# ESP32Cam-Programmer-Public.net
KiCad netlist of a schematic drawn in EAGLE
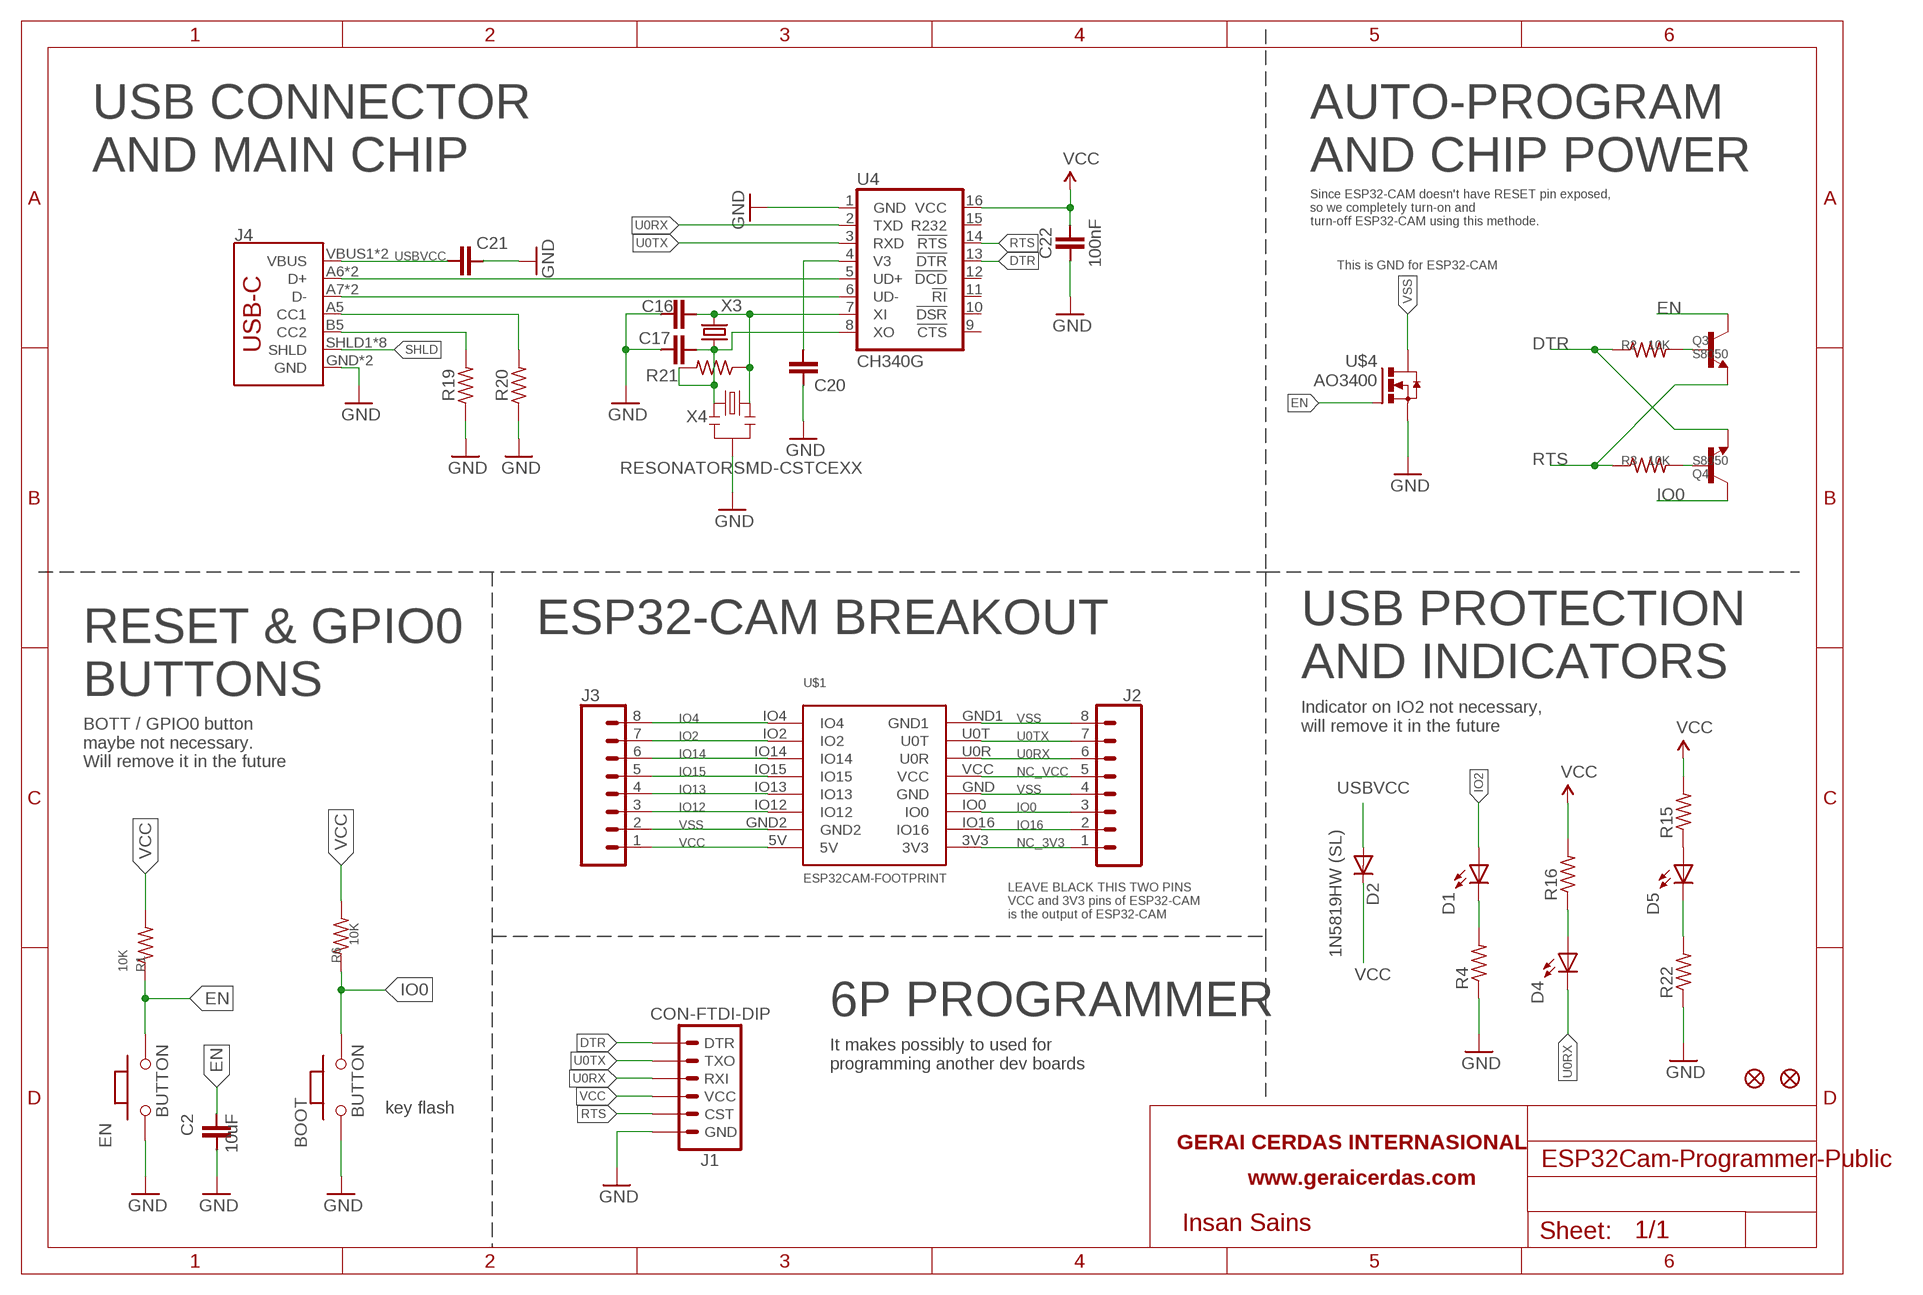
[diagram p0: schematic, sheet 1]

(export (version "E")
  (design (tool "Eeschema 10.0.6"))
  (components
    (comp (ref "BOOT")
      (value "BUTTON")
      (footprint "eagle-import:157SW")
      (libsource (lib "eagle-import") (part "PB157"))
    )
    (comp (ref "C2")
      (value "10uF")
      (footprint "eagle-import:C0603")
      (libsource (lib "eagle-import") (part "CAPACITOR-SMD0603"))
    )
    (comp (ref "C16")
      (value "10pF")
      (footprint "eagle-import:C0603")
      (libsource (lib "eagle-import") (part "CAPACITOR-SMD0603"))
    )
    (comp (ref "C17")
      (value "10pF")
      (footprint "eagle-import:C0603")
      (libsource (lib "eagle-import") (part "CAPACITOR-SMD0603"))
    )
    (comp (ref "C20")
      (value "10nF")
      (footprint "eagle-import:C0603")
      (libsource (lib "eagle-import") (part "CAPACITOR-SMD0603"))
    )
    (comp (ref "C21")
      (value "100nF")
      (footprint "eagle-import:C0603")
      (libsource (lib "eagle-import") (part "CAPACITOR-SMD0603"))
    )
    (comp (ref "C22")
      (value "100nF")
      (footprint "eagle-import:C0603")
      (libsource (lib "eagle-import") (part "CAPACITOR-SMD0603"))
    )
    (comp (ref "D1")
      (value "Yellow")
      (footprint "eagle-import:LED0805")
      (libsource (lib "eagle-import") (part "LED-SMD0805"))
    )
    (comp (ref "D2")
      (value "1N5819HW (SL)")
      (footprint "eagle-import:SOD-323")
      (fields (field (name "MANUFACTURER_PART_NUMBER") "1N4148WS"))
      (libsource (lib "eagle-import") (part "DIODE-1N4148-323"))
    )
    (comp (ref "D4")
      (value "GREEN")
      (footprint "eagle-import:LED0805")
      (libsource (lib "eagle-import") (part "LED-SMD0805"))
    )
    (comp (ref "D5")
      (value "Yellow")
      (footprint "eagle-import:LED0805")
      (libsource (lib "eagle-import") (part "LED-SMD0805"))
    )
    (comp (ref "EN")
      (value "BUTTON")
      (footprint "eagle-import:157SW")
      (libsource (lib "eagle-import") (part "PB157"))
    )
    (comp (ref "J1")
      (value "CON-FTDI-DIP")
      (footprint "eagle-import:CON-FTDI")
      (libsource (lib "eagle-import") (part "CON-FTDI-DIP"))
    )
    (comp (ref "J2")
      (value "CONN_08\"")
      (footprint "eagle-import:1X08")
      (libsource (lib "eagle-import") (part "CONN_08{dblquote}"))
    )
    (comp (ref "J3")
      (value "CONN_08\"")
      (footprint "eagle-import:1X08")
      (libsource (lib "eagle-import") (part "CONN_08{dblquote}"))
    )
    (comp (ref "J4")
      (value "USB_C16PIN")
      (footprint "eagle-import:USB-C-16P")
      (libsource (lib "eagle-import") (part "USB_C16PIN"))
    )
    (comp (ref "JP8")
      (value "FIDUCIAL1X2")
      (footprint "eagle-import:FIDUCIAL-1X2")
      (libsource (lib "eagle-import") (part "FIDUCIAL1X2"))
    )
    (comp (ref "JP9")
      (value "FIDUCIAL1X2")
      (footprint "eagle-import:FIDUCIAL-1X2")
      (libsource (lib "eagle-import") (part "FIDUCIAL1X2"))
    )
    (comp (ref "Q3")
      (value "S8050")
      (footprint "eagle-import:SOT-23")
      (libsource (lib "eagle-import") (part "TRANSISTOR-NPN-S8050"))
    )
    (comp (ref "Q4")
      (value "S8050")
      (footprint "eagle-import:SOT-23")
      (libsource (lib "eagle-import") (part "TRANSISTOR-NPN-S8050"))
    )
    (comp (ref "R1")
      (value "10K")
      (footprint "eagle-import:R0603")
      (libsource (lib "eagle-import") (part "RESISTOR-SMD0603"))
    )
    (comp (ref "R2")
      (value "10K")
      (footprint "eagle-import:R0603")
      (libsource (lib "eagle-import") (part "RESISTOR-SMD0603"))
    )
    (comp (ref "R3")
      (value "10K")
      (footprint "eagle-import:R0603")
      (libsource (lib "eagle-import") (part "RESISTOR-SMD0603"))
    )
    (comp (ref "R4")
      (value "1K")
      (footprint "eagle-import:R0603")
      (libsource (lib "eagle-import") (part "RESISTOR-SMD0603"))
    )
    (comp (ref "R6")
      (value "10K")
      (footprint "eagle-import:R0603")
      (libsource (lib "eagle-import") (part "RESISTOR-SMD0603"))
    )
    (comp (ref "R15")
      (value "330")
      (footprint "eagle-import:R0603")
      (libsource (lib "eagle-import") (part "RESISTOR-SMD0603"))
    )
    (comp (ref "R16")
      (value "330")
      (footprint "eagle-import:R0603")
      (libsource (lib "eagle-import") (part "RESISTOR-SMD0603"))
    )
    (comp (ref "R19")
      (value "5.1k")
      (footprint "eagle-import:R0603")
      (libsource (lib "eagle-import") (part "RESISTOR-SMD0603"))
    )
    (comp (ref "R20")
      (value "5.1k")
      (footprint "eagle-import:R0603")
      (libsource (lib "eagle-import") (part "RESISTOR-SMD0603"))
    )
    (comp (ref "R21")
      (value "RESISTOR-SMD0603")
      (footprint "eagle-import:R0603")
      (libsource (lib "eagle-import") (part "RESISTOR-SMD0603"))
    )
    (comp (ref "R22")
      (value "1K")
      (footprint "eagle-import:R0603")
      (libsource (lib "eagle-import") (part "RESISTOR-SMD0603"))
    )
    (comp (ref "U$1")
      (value "ESP32CAM-FOOTPRINT")
      (footprint "eagle-import:ESP32CAM")
      (libsource (lib "eagle-import") (part "ESP32CAM-FOOTPRINT"))
    )
    (comp (ref "U$4")
      (value "AO3400")
      (footprint "eagle-import:SOT-23")
      (libsource (lib "eagle-import") (part "AO3400"))
    )
    (comp (ref "U$13")
      (value "FRAME")
      (footprint "eagle-import:A4-HOR")
      (libsource (lib "eagle-import") (part "FRAME"))
    )
    (comp (ref "U4")
      (value "CH340G")
      (footprint "eagle-import:SO016")
      (libsource (lib "eagle-import") (part "CH340GSMD"))
    )
    (comp (ref "X3")
      (value "XTAL-SMD")
      (footprint "eagle-import:SMD-CRYSTAL")
      (libsource (lib "eagle-import") (part "XTAL-SMD"))
    )
    (comp (ref "X4")
      (value "RESONATORSMD-CSTCEXX")
      (footprint "eagle-import:CSTCE_")
      (libsource (lib "eagle-import") (part "RESONATORSMD-CSTCEXX"))
    )
  )
  (nets
    (net (code "1") (name "/IO4") (class "Default")
      (node (ref "J3") (pin "8") (pinfunction "8_8") (pintype "passive"))
      (node (ref "U$1") (pin "IO4") (pinfunction "IO4_IO4") (pintype "bidirectional"))
    )
    (net (code "2") (name "/IO12") (class "Default")
      (node (ref "J3") (pin "3") (pinfunction "3_3") (pintype "passive"))
      (node (ref "U$1") (pin "IO12") (pinfunction "IO12_IO12") (pintype "bidirectional"))
    )
    (net (code "3") (name "/IO13") (class "Default")
      (node (ref "J3") (pin "4") (pinfunction "4_4") (pintype "passive"))
      (node (ref "U$1") (pin "IO13") (pinfunction "IO13_IO13") (pintype "bidirectional"))
    )
    (net (code "4") (name "/IO14") (class "Default")
      (node (ref "J3") (pin "6") (pinfunction "6_6") (pintype "passive"))
      (node (ref "U$1") (pin "IO14") (pinfunction "IO14_IO14") (pintype "bidirectional"))
    )
    (net (code "5") (name "/IO15") (class "Default")
      (node (ref "J3") (pin "5") (pinfunction "5_5") (pintype "passive"))
      (node (ref "U$1") (pin "IO15") (pinfunction "IO15_IO15") (pintype "bidirectional"))
    )
    (net (code "6") (name "/IO16") (class "Default")
      (node (ref "J2") (pin "2") (pinfunction "2_2") (pintype "passive"))
      (node (ref "U$1") (pin "IO16") (pinfunction "IO16_IO16") (pintype "bidirectional"))
    )
    (net (code "7") (name "/NC_3V3") (class "Default")
      (node (ref "J2") (pin "1") (pinfunction "1_1") (pintype "passive"))
      (node (ref "U$1") (pin "3V3") (pinfunction "3V3_3V3") (pintype "bidirectional"))
    )
    (net (code "8") (name "/NC_VCC") (class "Default")
      (node (ref "J2") (pin "5") (pinfunction "5_5") (pintype "passive"))
      (node (ref "U$1") (pin "VCC") (pinfunction "VCC_VCC") (pintype "bidirectional"))
    )
    (net (code "9") (name "/USBVCC") (class "Default")
      (node (ref "C21") (pin "1") (pinfunction "1_1") (pintype "passive"))
      (node (ref "D2") (pin "A") (pinfunction "A_A") (pintype "passive"))
      (node (ref "J4") (pin "VBUS1") (pinfunction "VBUS_VBUS1") (pintype "bidirectional"))
      (node (ref "J4") (pin "VBUS2") (pinfunction "VBUS_VBUS2") (pintype "bidirectional"))
    )
    (net (code "10") (name "DTR") (class "Default")
      (node (ref "J1") (pin "DTR") (pinfunction "DTR_DTR") (pintype "passive"))
      (node (ref "Q4") (pin "2") (pinfunction "E_2") (pintype "passive"))
      (node (ref "R2") (pin "1") (pinfunction "1_1") (pintype "passive"))
      (node (ref "U4") (pin "13") (pinfunction "~{DTR}_13") (pintype "bidirectional"))
    )
    (net (code "11") (name "EN") (class "Default")
      (node (ref "C2") (pin "2") (pinfunction "2_2") (pintype "passive"))
      (node (ref "EN") (pin "2") (pinfunction "2_2") (pintype "passive"))
      (node (ref "Q3") (pin "3") (pinfunction "C_3") (pintype "passive"))
      (node (ref "R1") (pin "1") (pinfunction "1_1") (pintype "passive"))
      (node (ref "U$4") (pin "1") (pinfunction "G_1") (pintype "passive"))
    )
    (net (code "12") (name "GND") (class "Default")
      (node (ref "BOOT") (pin "1") (pinfunction "1_1") (pintype "passive"))
      (node (ref "C16") (pin "1") (pinfunction "1_1") (pintype "passive"))
      (node (ref "C17") (pin "1") (pinfunction "1_1") (pintype "passive"))
      (node (ref "C2") (pin "1") (pinfunction "1_1") (pintype "passive"))
      (node (ref "C20") (pin "2") (pinfunction "2_2") (pintype "passive"))
      (node (ref "C21") (pin "2") (pinfunction "2_2") (pintype "passive"))
      (node (ref "C22") (pin "1") (pinfunction "1_1") (pintype "passive"))
      (node (ref "EN") (pin "1") (pinfunction "1_1") (pintype "passive"))
      (node (ref "J1") (pin "GND") (pinfunction "GND_GND") (pintype "passive"))
      (node (ref "J4") (pin "GND") (pinfunction "GND_GND") (pintype "bidirectional"))
      (node (ref "J4") (pin "GND2") (pinfunction "GND_GND2") (pintype "bidirectional"))
      (node (ref "R19") (pin "1") (pinfunction "1_1") (pintype "passive"))
      (node (ref "R20") (pin "1") (pinfunction "1_1") (pintype "passive"))
      (node (ref "R22") (pin "1") (pinfunction "1_1") (pintype "passive"))
      (node (ref "R4") (pin "1") (pinfunction "1_1") (pintype "passive"))
      (node (ref "U$4") (pin "2") (pinfunction "S_2") (pintype "passive"))
      (node (ref "U4") (pin "1") (pinfunction "GND_1") (pintype "bidirectional"))
      (node (ref "X4") (pin "2") (pinfunction "2_2") (pintype "passive"))
    )
    (net (code "13") (name "IO0") (class "Default")
      (node (ref "BOOT") (pin "2") (pinfunction "2_2") (pintype "passive"))
      (node (ref "J2") (pin "3") (pinfunction "3_3") (pintype "passive"))
      (node (ref "Q4") (pin "3") (pinfunction "C_3") (pintype "passive"))
      (node (ref "R6") (pin "1") (pinfunction "1_1") (pintype "passive"))
      (node (ref "U$1") (pin "IO0") (pinfunction "IO0_IO0") (pintype "bidirectional"))
    )
    (net (code "14") (name "IO2") (class "Default")
      (node (ref "D1") (pin "A") (pinfunction "A_A") (pintype "passive"))
      (node (ref "J3") (pin "7") (pinfunction "7_7") (pintype "passive"))
      (node (ref "U$1") (pin "IO2") (pinfunction "IO2_IO2") (pintype "bidirectional"))
    )
    (net (code "15") (name "Net-(D1-PadC)") (class "Default")
      (node (ref "D1") (pin "C") (pinfunction "C_C") (pintype "passive"))
      (node (ref "R4") (pin "2") (pinfunction "2_2") (pintype "passive"))
    )
    (net (code "16") (name "Net-(D4-PadA)") (class "Default")
      (node (ref "D4") (pin "A") (pinfunction "A_A") (pintype "passive"))
      (node (ref "R16") (pin "1") (pinfunction "1_1") (pintype "passive"))
    )
    (net (code "17") (name "Net-(D5-PadA)") (class "Default")
      (node (ref "D5") (pin "A") (pinfunction "A_A") (pintype "passive"))
      (node (ref "R15") (pin "1") (pinfunction "1_1") (pintype "passive"))
    )
    (net (code "18") (name "Net-(D5-PadC)") (class "Default")
      (node (ref "D5") (pin "C") (pinfunction "C_C") (pintype "passive"))
      (node (ref "R22") (pin "2") (pinfunction "2_2") (pintype "passive"))
    )
    (net (code "19") (name "Net-(J4-CC1)") (class "Default")
      (node (ref "J4") (pin "A5") (pinfunction "CC1_A5") (pintype "bidirectional"))
      (node (ref "R20") (pin "2") (pinfunction "2_2") (pintype "passive"))
    )
    (net (code "20") (name "Net-(J4-CC2)") (class "Default")
      (node (ref "J4") (pin "B5") (pinfunction "CC2_B5") (pintype "bidirectional"))
      (node (ref "R19") (pin "2") (pinfunction "2_2") (pintype "passive"))
    )
    (net (code "21") (name "Net-(Q3-B)") (class "Default")
      (node (ref "Q3") (pin "1") (pinfunction "B_1") (pintype "passive"))
      (node (ref "R2") (pin "2") (pinfunction "2_2") (pintype "passive"))
    )
    (net (code "22") (name "Net-(Q4-B)") (class "Default")
      (node (ref "Q4") (pin "1") (pinfunction "B_1") (pintype "passive"))
      (node (ref "R3") (pin "2") (pinfunction "2_2") (pintype "passive"))
    )
    (net (code "23") (name "Net-(U4-UD+)") (class "Default")
      (node (ref "J4") (pin "A6") (pinfunction "D+_A6") (pintype "bidirectional"))
      (node (ref "J4") (pin "B6") (pinfunction "D+_B6") (pintype "bidirectional"))
      (node (ref "U4") (pin "5") (pinfunction "UD+_5") (pintype "bidirectional"))
    )
    (net (code "24") (name "Net-(U4-UD-)") (class "Default")
      (node (ref "J4") (pin "A7") (pinfunction "D-_A7") (pintype "bidirectional"))
      (node (ref "J4") (pin "B7") (pinfunction "D-_B7") (pintype "bidirectional"))
      (node (ref "U4") (pin "6") (pinfunction "UD-_6") (pintype "bidirectional"))
    )
    (net (code "25") (name "Net-(U4-V3)") (class "Default")
      (node (ref "C20") (pin "1") (pinfunction "1_1") (pintype "passive"))
      (node (ref "U4") (pin "4") (pinfunction "V3_4") (pintype "bidirectional"))
    )
    (net (code "26") (name "Net-(U4-XI)") (class "Default")
      (node (ref "C16") (pin "2") (pinfunction "2_2") (pintype "passive"))
      (node (ref "R21") (pin "1") (pinfunction "1_1") (pintype "passive"))
      (node (ref "U4") (pin "7") (pinfunction "XI_7") (pintype "bidirectional"))
      (node (ref "X3") (pin "2") (pinfunction "2_2") (pintype "passive"))
      (node (ref "X4") (pin "3") (pinfunction "3_3") (pintype "passive"))
    )
    (net (code "27") (name "Net-(U4-XO)") (class "Default")
      (node (ref "C17") (pin "2") (pinfunction "2_2") (pintype "passive"))
      (node (ref "R21") (pin "2") (pinfunction "2_2") (pintype "passive"))
      (node (ref "U4") (pin "8") (pinfunction "XO_8") (pintype "bidirectional"))
      (node (ref "X3") (pin "1") (pinfunction "1_1") (pintype "passive"))
      (node (ref "X4") (pin "1") (pinfunction "1_1") (pintype "passive"))
    )
    (net (code "28") (name "RTS") (class "Default")
      (node (ref "J1") (pin "CTS") (pinfunction "CST_CTS") (pintype "passive"))
      (node (ref "Q3") (pin "2") (pinfunction "E_2") (pintype "passive"))
      (node (ref "R3") (pin "1") (pinfunction "1_1") (pintype "passive"))
      (node (ref "U4") (pin "14") (pinfunction "~{RTS}_14") (pintype "bidirectional"))
    )
    (net (code "29") (name "SHLD") (class "Default")
      (node (ref "J4") (pin "SHLD1") (pinfunction "SHLD_SHLD1") (pintype "bidirectional"))
      (node (ref "J4") (pin "SHLD2") (pinfunction "SHLD_SHLD2") (pintype "bidirectional"))
      (node (ref "J4") (pin "SHLD3") (pinfunction "SHLD_SHLD3") (pintype "bidirectional"))
      (node (ref "J4") (pin "SHLD4") (pinfunction "SHLD_SHLD4") (pintype "bidirectional"))
      (node (ref "J4") (pin "SHLD5") (pinfunction "SHLD_SHLD5") (pintype "bidirectional"))
      (node (ref "J4") (pin "SHLD6") (pinfunction "SHLD_SHLD6") (pintype "bidirectional"))
      (node (ref "J4") (pin "SHLD7") (pinfunction "SHLD_SHLD7") (pintype "bidirectional"))
      (node (ref "J4") (pin "SHLD8") (pinfunction "SHLD_SHLD8") (pintype "bidirectional"))
    )
    (net (code "30") (name "U0RX") (class "Default")
      (node (ref "D4") (pin "C") (pinfunction "C_C") (pintype "passive"))
      (node (ref "J1") (pin "RXI") (pinfunction "RXI_RXI") (pintype "passive"))
      (node (ref "J2") (pin "6") (pinfunction "6_6") (pintype "passive"))
      (node (ref "U$1") (pin "U0R") (pinfunction "U0R_U0R") (pintype "bidirectional"))
      (node (ref "U4") (pin "2") (pinfunction "TXD_2") (pintype "bidirectional"))
    )
    (net (code "31") (name "U0TX") (class "Default")
      (node (ref "J1") (pin "TX0") (pinfunction "TXO_TX0") (pintype "passive"))
      (node (ref "J2") (pin "7") (pinfunction "7_7") (pintype "passive"))
      (node (ref "U$1") (pin "U0T") (pinfunction "U0T_U0T") (pintype "bidirectional"))
      (node (ref "U4") (pin "3") (pinfunction "RXD_3") (pintype "bidirectional"))
    )
    (net (code "32") (name "VCC") (class "Default")
      (node (ref "C22") (pin "2") (pinfunction "2_2") (pintype "passive"))
      (node (ref "D2") (pin "C") (pinfunction "C_C") (pintype "passive"))
      (node (ref "J1") (pin "VCC") (pinfunction "VCC_VCC") (pintype "passive"))
      (node (ref "J3") (pin "1") (pinfunction "1_1") (pintype "passive"))
      (node (ref "R1") (pin "2") (pinfunction "2_2") (pintype "passive"))
      (node (ref "R15") (pin "2") (pinfunction "2_2") (pintype "passive"))
      (node (ref "R16") (pin "2") (pinfunction "2_2") (pintype "passive"))
      (node (ref "R6") (pin "2") (pinfunction "2_2") (pintype "passive"))
      (node (ref "U$1") (pin "5V") (pinfunction "5V_5V") (pintype "bidirectional"))
      (node (ref "U4") (pin "16") (pinfunction "VCC_16") (pintype "bidirectional"))
    )
    (net (code "33") (name "VSS") (class "Default")
      (node (ref "J2") (pin "4") (pinfunction "4_4") (pintype "passive"))
      (node (ref "J2") (pin "8") (pinfunction "8_8") (pintype "passive"))
      (node (ref "J3") (pin "2") (pinfunction "2_2") (pintype "passive"))
      (node (ref "U$1") (pin "GND") (pinfunction "GND_GND") (pintype "bidirectional"))
      (node (ref "U$1") (pin "GND1") (pinfunction "GND1_GND1") (pintype "bidirectional"))
      (node (ref "U$1") (pin "GND2") (pinfunction "GND2_GND2") (pintype "bidirectional"))
      (node (ref "U$4") (pin "3") (pinfunction "D_3") (pintype "passive"))
    )
    (net (code "34") (name "unconnected-(U4-R232-Pad15)") (class "Default")
      (node (ref "U4") (pin "15") (pinfunction "R232_15") (pintype "bidirectional"))
    )
    (net (code "35") (name "unconnected-(U4-~{CTS}-Pad9)") (class "Default")
      (node (ref "U4") (pin "9") (pinfunction "~{CTS}_9") (pintype "bidirectional"))
    )
    (net (code "36") (name "unconnected-(U4-~{DCD}-Pad12)") (class "Default")
      (node (ref "U4") (pin "12") (pinfunction "~{DCD}_12") (pintype "bidirectional"))
    )
    (net (code "37") (name "unconnected-(U4-~{DSR}-Pad10)") (class "Default")
      (node (ref "U4") (pin "10") (pinfunction "~{DSR}_10") (pintype "bidirectional"))
    )
    (net (code "38") (name "unconnected-(U4-~{RI}-Pad11)") (class "Default")
      (node (ref "U4") (pin "11") (pinfunction "~{RI}_11") (pintype "bidirectional"))
    )
  )
)
